# leslius.net
KiCad netlist of a schematic drawn in EAGLE
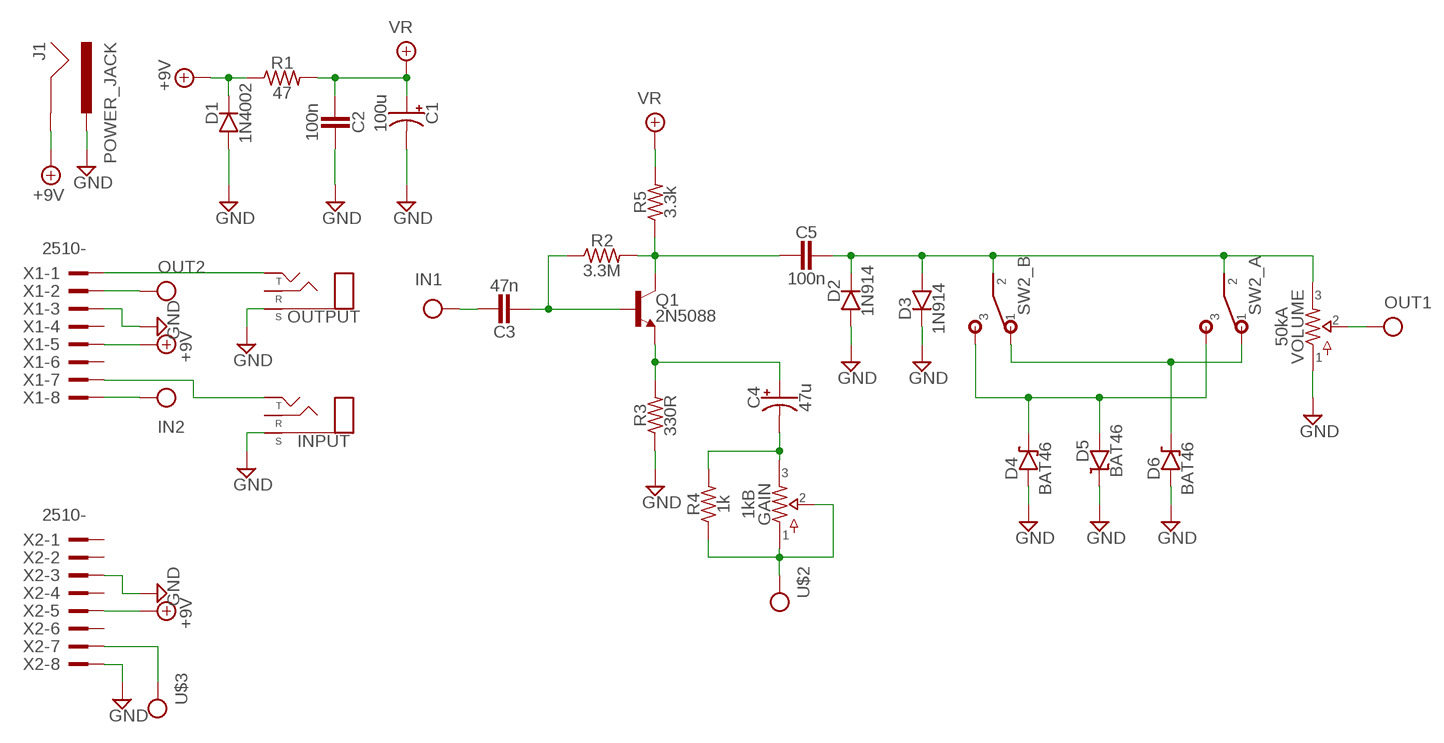
[diagram p0: schematic, sheet 1]

(export (version "E")
  (design (tool "Eeschema 10.0.6"))
  (components
    (comp (ref "C1")
      (value "100u")
      (footprint "eagle-import:040_020")
      (libsource (lib "eagle-import") (part "0400"))
    )
    (comp (ref "C2")
      (value "100n")
      (footprint "eagle-import:050X030_025_2")
      (libsource (lib "eagle-import") (part "CER/FILM2"))
    )
    (comp (ref "C3")
      (value "47n")
      (footprint "eagle-import:BOX_SMALL")
      (libsource (lib "eagle-import") (part "CER/FILMBOX.1"))
    )
    (comp (ref "C4")
      (value "47u")
      (footprint "eagle-import:040_020")
      (libsource (lib "eagle-import") (part "0400"))
    )
    (comp (ref "C5")
      (value "100n")
      (footprint "eagle-import:BOX_SMALL")
      (libsource (lib "eagle-import") (part "CER/FILMBOX.1"))
    )
    (comp (ref "D1")
      (value "1N4002")
      (footprint "eagle-import:DO41-2")
      (libsource (lib "eagle-import") (part "DO41.2"))
    )
    (comp (ref "D2")
      (value "1N914")
      (footprint "eagle-import:DO35-2")
      (libsource (lib "eagle-import") (part "DO35.2"))
    )
    (comp (ref "D3")
      (value "1N914")
      (footprint "eagle-import:DO35-2")
      (libsource (lib "eagle-import") (part "DO35.2"))
    )
    (comp (ref "D4")
      (value "BAT46")
      (footprint "eagle-import:DO41-2")
      (libsource (lib "eagle-import") (part "ZENER.2"))
    )
    (comp (ref "D5")
      (value "BAT46")
      (footprint "eagle-import:DO41-2")
      (libsource (lib "eagle-import") (part "ZENER.2"))
    )
    (comp (ref "D6")
      (value "BAT46")
      (footprint "eagle-import:DO41-2")
      (libsource (lib "eagle-import") (part "ZENER.2"))
    )
    (comp (ref "GAIN")
      (value "1kB")
      (footprint "eagle-import:16MM")
      (libsource (lib "eagle-import") (part "POTS16MM"))
    )
    (comp (ref "INPUT")
      (value "STEREONMJ")
      (footprint "eagle-import:NMJ6HCD2")
      (libsource (lib "eagle-import") (part "STEREONMJ"))
    )
    (comp (ref "J1")
      (value "POWER_JACK")
      (footprint "eagle-import:POWER_JACK_PTH")
      (libsource (lib "eagle-import") (part "POWER_JACK"))
    )
    (comp (ref "OUTPUT")
      (value "STEREONMJ")
      (footprint "eagle-import:NMJ6HCD2")
      (libsource (lib "eagle-import") (part "STEREONMJ"))
    )
    (comp (ref "Q1")
      (value "2N5088")
      (footprint "eagle-import:TO92-")
      (libsource (lib "eagle-import") (part "2N5088"))
    )
    (comp (ref "R1")
      (value "47")
      (footprint "eagle-import:R0207_3")
      (libsource (lib "eagle-import") (part "R_.3B"))
    )
    (comp (ref "R2")
      (value "3.3M")
      (footprint "eagle-import:R0207_3")
      (libsource (lib "eagle-import") (part "R_.3B"))
    )
    (comp (ref "R3")
      (value "330R")
      (footprint "eagle-import:R0207_3")
      (libsource (lib "eagle-import") (part "R_.3B"))
    )
    (comp (ref "R4")
      (value "1k")
      (footprint "eagle-import:R0207_3")
      (libsource (lib "eagle-import") (part "R_.3B"))
    )
    (comp (ref "R5")
      (value "3.3k")
      (footprint "eagle-import:R0207_3")
      (libsource (lib "eagle-import") (part "R_.3B"))
    )
    (comp (ref "SW2")
      (value "DPDT")
      (footprint "eagle-import:DPDT")
      (libsource (lib "eagle-import") (part "DPDT"))
    )
    (comp (ref "VOLUME")
      (value "50kA")
      (footprint "eagle-import:16MM")
      (libsource (lib "eagle-import") (part "POTS16MM"))
    )
    (comp (ref "X1")
      (value "2510-")
      (footprint "eagle-import:PAK100_2500-10")
      (fields (field (name "MF") "3M") (field (name "MPN") "2510-6002UB"))
      (libsource (lib "eagle-import") (part "2510-"))
    )
    (comp (ref "X2")
      (value "2510-")
      (footprint "eagle-import:PAK100_2500-10")
      (fields (field (name "MF") "3M") (field (name "MPN") "2510-6002UB"))
      (libsource (lib "eagle-import") (part "2510-"))
    )
  )
  (nets
    (net (code "1") (name "+9V") (class "Default")
      (node (ref "D1") (pin "C") (pinfunction "C_C") (pintype "passive"))
      (node (ref "J1") (pin "GND") (pinfunction "GND_GND") (pintype "bidirectional"))
      (node (ref "R1") (pin "1") (pinfunction "1_1") (pintype "passive"))
      (node (ref "X1") (pin "5") (pinfunction "KL_5") (pintype "passive"))
      (node (ref "X2") (pin "5") (pinfunction "KL_5") (pintype "passive"))
    )
    (net (code "2") (name "GND") (class "Default")
      (node (ref "C1") (pin "-") (pinfunction "-_-") (pintype "passive"))
      (node (ref "C2") (pin "1") (pinfunction "1_1") (pintype "passive"))
      (node (ref "D1") (pin "A") (pinfunction "A_A") (pintype "passive"))
      (node (ref "D2") (pin "A") (pinfunction "A_A") (pintype "passive"))
      (node (ref "D3") (pin "C") (pinfunction "C_C") (pintype "passive"))
      (node (ref "D4") (pin "A") (pinfunction "A_A") (pintype "passive"))
      (node (ref "D5") (pin "C") (pinfunction "C_C") (pintype "passive"))
      (node (ref "D6") (pin "A") (pinfunction "A_A") (pintype "passive"))
      (node (ref "INPUT") (pin "S") (pinfunction "S_S") (pintype "passive"))
      (node (ref "J1") (pin "PWR") (pinfunction "PWR_PWR") (pintype "bidirectional"))
      (node (ref "OUTPUT") (pin "S") (pinfunction "S_S") (pintype "passive"))
      (node (ref "R3") (pin "1") (pinfunction "1_1") (pintype "passive"))
      (node (ref "VOLUME") (pin "1") (pinfunction "1_1") (pintype "passive"))
      (node (ref "X1") (pin "3") (pinfunction "KL_3") (pintype "passive"))
      (node (ref "X2") (pin "3") (pinfunction "KL_3") (pintype "passive"))
      (node (ref "X2") (pin "8") (pinfunction "KL_8") (pintype "passive"))
    )
    (net (code "3") (name "IN") (class "Default")
      (node (ref "C3") (pin "1") (pinfunction "1_1") (pintype "passive"))
      (node (ref "X1") (pin "8") (pinfunction "KL_8") (pintype "passive"))
    )
    (net (code "4") (name "Net-(C4-Pad-)") (class "Default")
      (node (ref "C4") (pin "-") (pinfunction "-_-") (pintype "passive"))
      (node (ref "GAIN") (pin "3") (pinfunction "3_3") (pintype "passive"))
      (node (ref "R4") (pin "2") (pinfunction "2_2") (pintype "passive"))
    )
    (net (code "5") (name "Net-(Q1-B)") (class "Default")
      (node (ref "C3") (pin "2") (pinfunction "2_2") (pintype "passive"))
      (node (ref "Q1") (pin "2") (pinfunction "B_2") (pintype "passive"))
      (node (ref "R2") (pin "1") (pinfunction "1_1") (pintype "passive"))
    )
    (net (code "6") (name "Net-(Q1-C)") (class "Default")
      (node (ref "C5") (pin "1") (pinfunction "1_1") (pintype "passive"))
      (node (ref "Q1") (pin "1") (pinfunction "C_1") (pintype "passive"))
      (node (ref "R2") (pin "2") (pinfunction "2_2") (pintype "passive"))
      (node (ref "R5") (pin "1") (pinfunction "1_1") (pintype "passive"))
    )
    (net (code "7") (name "Net-(Q1-E)") (class "Default")
      (node (ref "C4") (pin "+") (pinfunction "+_+") (pintype "passive"))
      (node (ref "Q1") (pin "3") (pinfunction "E_3") (pintype "passive"))
      (node (ref "R3") (pin "2") (pinfunction "2_2") (pintype "passive"))
    )
    (net (code "8") (name "Net-(SW2A-1)") (class "Default")
      (node (ref "D6") (pin "C") (pinfunction "C_C") (pintype "passive"))
      (node (ref "SW2") (pin "A1") (pinfunction "1_A1") (pintype "passive"))
      (node (ref "SW2") (pin "B1") (pinfunction "1_B1") (pintype "passive"))
    )
    (net (code "9") (name "Net-(SW2A-2)") (class "Default")
      (node (ref "C5") (pin "2") (pinfunction "2_2") (pintype "passive"))
      (node (ref "D2") (pin "C") (pinfunction "C_C") (pintype "passive"))
      (node (ref "D3") (pin "A") (pinfunction "A_A") (pintype "passive"))
      (node (ref "SW2") (pin "A2") (pinfunction "2_A2") (pintype "passive"))
      (node (ref "SW2") (pin "B2") (pinfunction "2_B2") (pintype "passive"))
      (node (ref "VOLUME") (pin "3") (pinfunction "3_3") (pintype "passive"))
    )
    (net (code "10") (name "Net-(SW2A-3)") (class "Default")
      (node (ref "D4") (pin "C") (pinfunction "C_C") (pintype "passive"))
      (node (ref "D5") (pin "A") (pinfunction "A_A") (pintype "passive"))
      (node (ref "SW2") (pin "A3") (pinfunction "3_A3") (pintype "passive"))
      (node (ref "SW2") (pin "B3") (pinfunction "3_B3") (pintype "passive"))
    )
    (net (code "11") (name "Net-(X1A-KL)") (class "Default")
      (node (ref "OUTPUT") (pin "T") (pinfunction "T_T") (pintype "passive"))
      (node (ref "X1") (pin "1") (pinfunction "KL_1") (pintype "passive"))
    )
    (net (code "12") (name "Net-(X1G-KL)") (class "Default")
      (node (ref "INPUT") (pin "T") (pinfunction "T_T") (pintype "passive"))
      (node (ref "X1") (pin "7") (pinfunction "KL_7") (pintype "passive"))
    )
    (net (code "13") (name "OUT") (class "Default")
      (node (ref "VOLUME") (pin "2") (pinfunction "2_2") (pintype "passive"))
      (node (ref "X1") (pin "2") (pinfunction "KL_2") (pintype "passive"))
    )
    (net (code "14") (name "SND") (class "Default")
      (node (ref "GAIN") (pin "1") (pinfunction "1_1") (pintype "passive"))
      (node (ref "GAIN") (pin "2") (pinfunction "2_2") (pintype "passive"))
      (node (ref "R4") (pin "1") (pinfunction "1_1") (pintype "passive"))
      (node (ref "X2") (pin "7") (pinfunction "KL_7") (pintype "passive"))
    )
    (net (code "15") (name "VR") (class "Default")
      (node (ref "C1") (pin "+") (pinfunction "+_+") (pintype "passive"))
      (node (ref "C2") (pin "2") (pinfunction "2_2") (pintype "passive"))
      (node (ref "R1") (pin "2") (pinfunction "2_2") (pintype "passive"))
      (node (ref "R5") (pin "2") (pinfunction "2_2") (pintype "passive"))
    )
    (net (code "16") (name "unconnected-(INPUT-PadR)") (class "Default")
      (node (ref "INPUT") (pin "R") (pinfunction "R_R") (pintype "passive"))
    )
    (net (code "17") (name "unconnected-(OUTPUT-PadR)") (class "Default")
      (node (ref "OUTPUT") (pin "R") (pinfunction "R_R") (pintype "passive"))
    )
    (net (code "18") (name "unconnected-(X1D-KL-Pad4)") (class "Default")
      (node (ref "X1") (pin "4") (pinfunction "KL_4") (pintype "passive"))
    )
    (net (code "19") (name "unconnected-(X1F-KL-Pad6)") (class "Default")
      (node (ref "X1") (pin "6") (pinfunction "KL_6") (pintype "passive"))
    )
    (net (code "20") (name "unconnected-(X2A-KL-Pad1)") (class "Default")
      (node (ref "X2") (pin "1") (pinfunction "KL_1") (pintype "passive"))
    )
    (net (code "21") (name "unconnected-(X2B-KL-Pad2)") (class "Default")
      (node (ref "X2") (pin "2") (pinfunction "KL_2") (pintype "passive"))
    )
    (net (code "22") (name "unconnected-(X2D-KL-Pad4)") (class "Default")
      (node (ref "X2") (pin "4") (pinfunction "KL_4") (pintype "passive"))
    )
    (net (code "23") (name "unconnected-(X2F-KL-Pad6)") (class "Default")
      (node (ref "X2") (pin "6") (pinfunction "KL_6") (pintype "passive"))
    )
  )
)
